# MA702.net
KiCad netlist of a schematic drawn in EAGLE
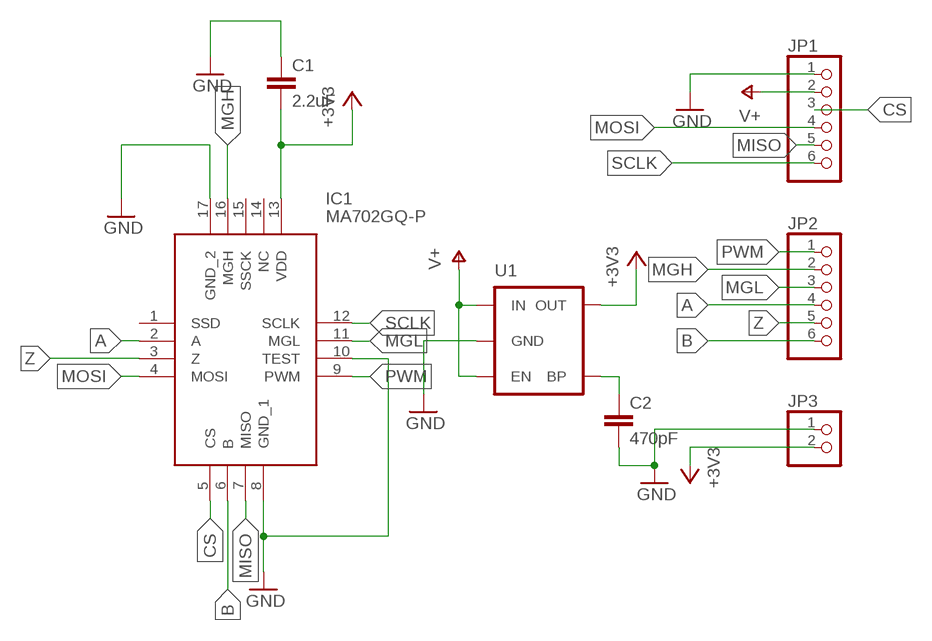
[diagram p0: schematic, sheet 1]

(export (version "E")
  (design (tool "Eeschema 10.0.6"))
  (components
    (comp (ref "C1")
      (value "2.2uF")
      (footprint "eagle-import:C0603")
      (libsource (lib "eagle-import") (part "C-EUC0603"))
    )
    (comp (ref "C2")
      (value "470pF")
      (footprint "eagle-import:C0603")
      (libsource (lib "eagle-import") (part "C-EUC0603"))
    )
    (comp (ref "IC1")
      (value "MA702GQ-P")
      (footprint "eagle-import:QFN50P300X300X100-17N")
      (fields (field (name "MOUSER_PART_NUMBER") "946-MA702GQ-P"))
      (libsource (lib "eagle-import") (part "MA702GQ-P"))
    )
    (comp (ref "JP1")
      (value "PINHD-1X06_2.54-S")
      (footprint "eagle-import:1X06-S")
      (libsource (lib "eagle-import") (part "PINHD-1X06_2.54-S"))
    )
    (comp (ref "JP2")
      (value "PINHD-1X06_2.54-S")
      (footprint "eagle-import:1X06-S")
      (libsource (lib "eagle-import") (part "PINHD-1X06_2.54-S"))
    )
    (comp (ref "JP3")
      (value "PINHD-1X02_2.54-S")
      (footprint "eagle-import:1X02-S")
      (libsource (lib "eagle-import") (part "PINHD-1X02_2.54-S"))
    )
    (comp (ref "U1")
      (value "SPARKFUN-POWERIC_MIC52053.3V")
      (footprint "eagle-import:SPARKFUN-POWERIC_SOT23-5")
      (libsource (lib "eagle-import") (part "SPARKFUN-POWERIC_MIC52053.3V"))
    )
  )
  (nets
    (net (code "1") (name "+3V3") (class "Default")
      (node (ref "C1") (pin "2") (pinfunction "2_2") (pintype "passive"))
      (node (ref "IC1") (pin "13") (pinfunction "VDD_13") (pintype "bidirectional"))
      (node (ref "JP3") (pin "2") (pinfunction "2_2") (pintype "passive"))
      (node (ref "U1") (pin "5") (pinfunction "OUT_5") (pintype "passive"))
    )
    (net (code "2") (name "A") (class "Default")
      (node (ref "IC1") (pin "2") (pinfunction "A_2") (pintype "bidirectional"))
      (node (ref "JP2") (pin "4") (pinfunction "4_4") (pintype "passive"))
    )
    (net (code "3") (name "B") (class "Default")
      (node (ref "IC1") (pin "6") (pinfunction "B_6") (pintype "bidirectional"))
      (node (ref "JP2") (pin "6") (pinfunction "6_6") (pintype "passive"))
    )
    (net (code "4") (name "CS") (class "Default")
      (node (ref "IC1") (pin "5") (pinfunction "CS_5") (pintype "bidirectional"))
      (node (ref "JP1") (pin "3") (pinfunction "3_3") (pintype "passive"))
    )
    (net (code "5") (name "GND") (class "Default")
      (node (ref "C1") (pin "1") (pinfunction "1_1") (pintype "passive"))
      (node (ref "C2") (pin "2") (pinfunction "2_2") (pintype "passive"))
      (node (ref "IC1") (pin "10") (pinfunction "TEST_10") (pintype "bidirectional"))
      (node (ref "IC1") (pin "17") (pinfunction "GND_2_17") (pintype "bidirectional"))
      (node (ref "IC1") (pin "8") (pinfunction "GND_1_8") (pintype "bidirectional"))
      (node (ref "JP1") (pin "1") (pinfunction "1_1") (pintype "passive"))
      (node (ref "JP3") (pin "1") (pinfunction "1_1") (pintype "passive"))
      (node (ref "U1") (pin "2") (pinfunction "GND_2") (pintype "input"))
    )
    (net (code "6") (name "MGH") (class "Default")
      (node (ref "IC1") (pin "16") (pinfunction "MGH_16") (pintype "bidirectional"))
      (node (ref "JP2") (pin "2") (pinfunction "2_2") (pintype "passive"))
    )
    (net (code "7") (name "MGL") (class "Default")
      (node (ref "IC1") (pin "11") (pinfunction "MGL_11") (pintype "bidirectional"))
      (node (ref "JP2") (pin "3") (pinfunction "3_3") (pintype "passive"))
    )
    (net (code "8") (name "MISO") (class "Default")
      (node (ref "IC1") (pin "7") (pinfunction "MISO_7") (pintype "bidirectional"))
      (node (ref "JP1") (pin "5") (pinfunction "5_5") (pintype "passive"))
    )
    (net (code "9") (name "MOSI") (class "Default")
      (node (ref "IC1") (pin "4") (pinfunction "MOSI_4") (pintype "bidirectional"))
      (node (ref "JP1") (pin "4") (pinfunction "4_4") (pintype "passive"))
    )
    (net (code "10") (name "Net-(U1-BP)") (class "Default")
      (node (ref "C2") (pin "1") (pinfunction "1_1") (pintype "passive"))
      (node (ref "U1") (pin "4") (pinfunction "BP_4") (pintype "input"))
    )
    (net (code "11") (name "PWM") (class "Default")
      (node (ref "IC1") (pin "9") (pinfunction "PWM_9") (pintype "bidirectional"))
      (node (ref "JP2") (pin "1") (pinfunction "1_1") (pintype "passive"))
    )
    (net (code "12") (name "SCLK") (class "Default")
      (node (ref "IC1") (pin "12") (pinfunction "SCLK_12") (pintype "bidirectional"))
      (node (ref "JP1") (pin "6") (pinfunction "6_6") (pintype "passive"))
    )
    (net (code "13") (name "V+") (class "Default")
      (node (ref "JP1") (pin "2") (pinfunction "2_2") (pintype "passive"))
      (node (ref "U1") (pin "1") (pinfunction "IN_1") (pintype "input"))
      (node (ref "U1") (pin "3") (pinfunction "EN_3") (pintype "input"))
    )
    (net (code "14") (name "Z") (class "Default")
      (node (ref "IC1") (pin "3") (pinfunction "Z_3") (pintype "bidirectional"))
      (node (ref "JP2") (pin "5") (pinfunction "5_5") (pintype "passive"))
    )
    (net (code "15") (name "unconnected-(IC1-NC-Pad14)") (class "Default")
      (node (ref "IC1") (pin "14") (pinfunction "NC_14") (pintype "no_connect"))
    )
    (net (code "16") (name "unconnected-(IC1-SSCK-Pad15)") (class "Default")
      (node (ref "IC1") (pin "15") (pinfunction "SSCK_15") (pintype "bidirectional"))
    )
    (net (code "17") (name "unconnected-(IC1-SSD-Pad1)") (class "Default")
      (node (ref "IC1") (pin "1") (pinfunction "SSD_1") (pintype "bidirectional"))
    )
  )
)
